# FishyUSBHub.net
KiCad netlist of a schematic drawn in EasyEDA Pro
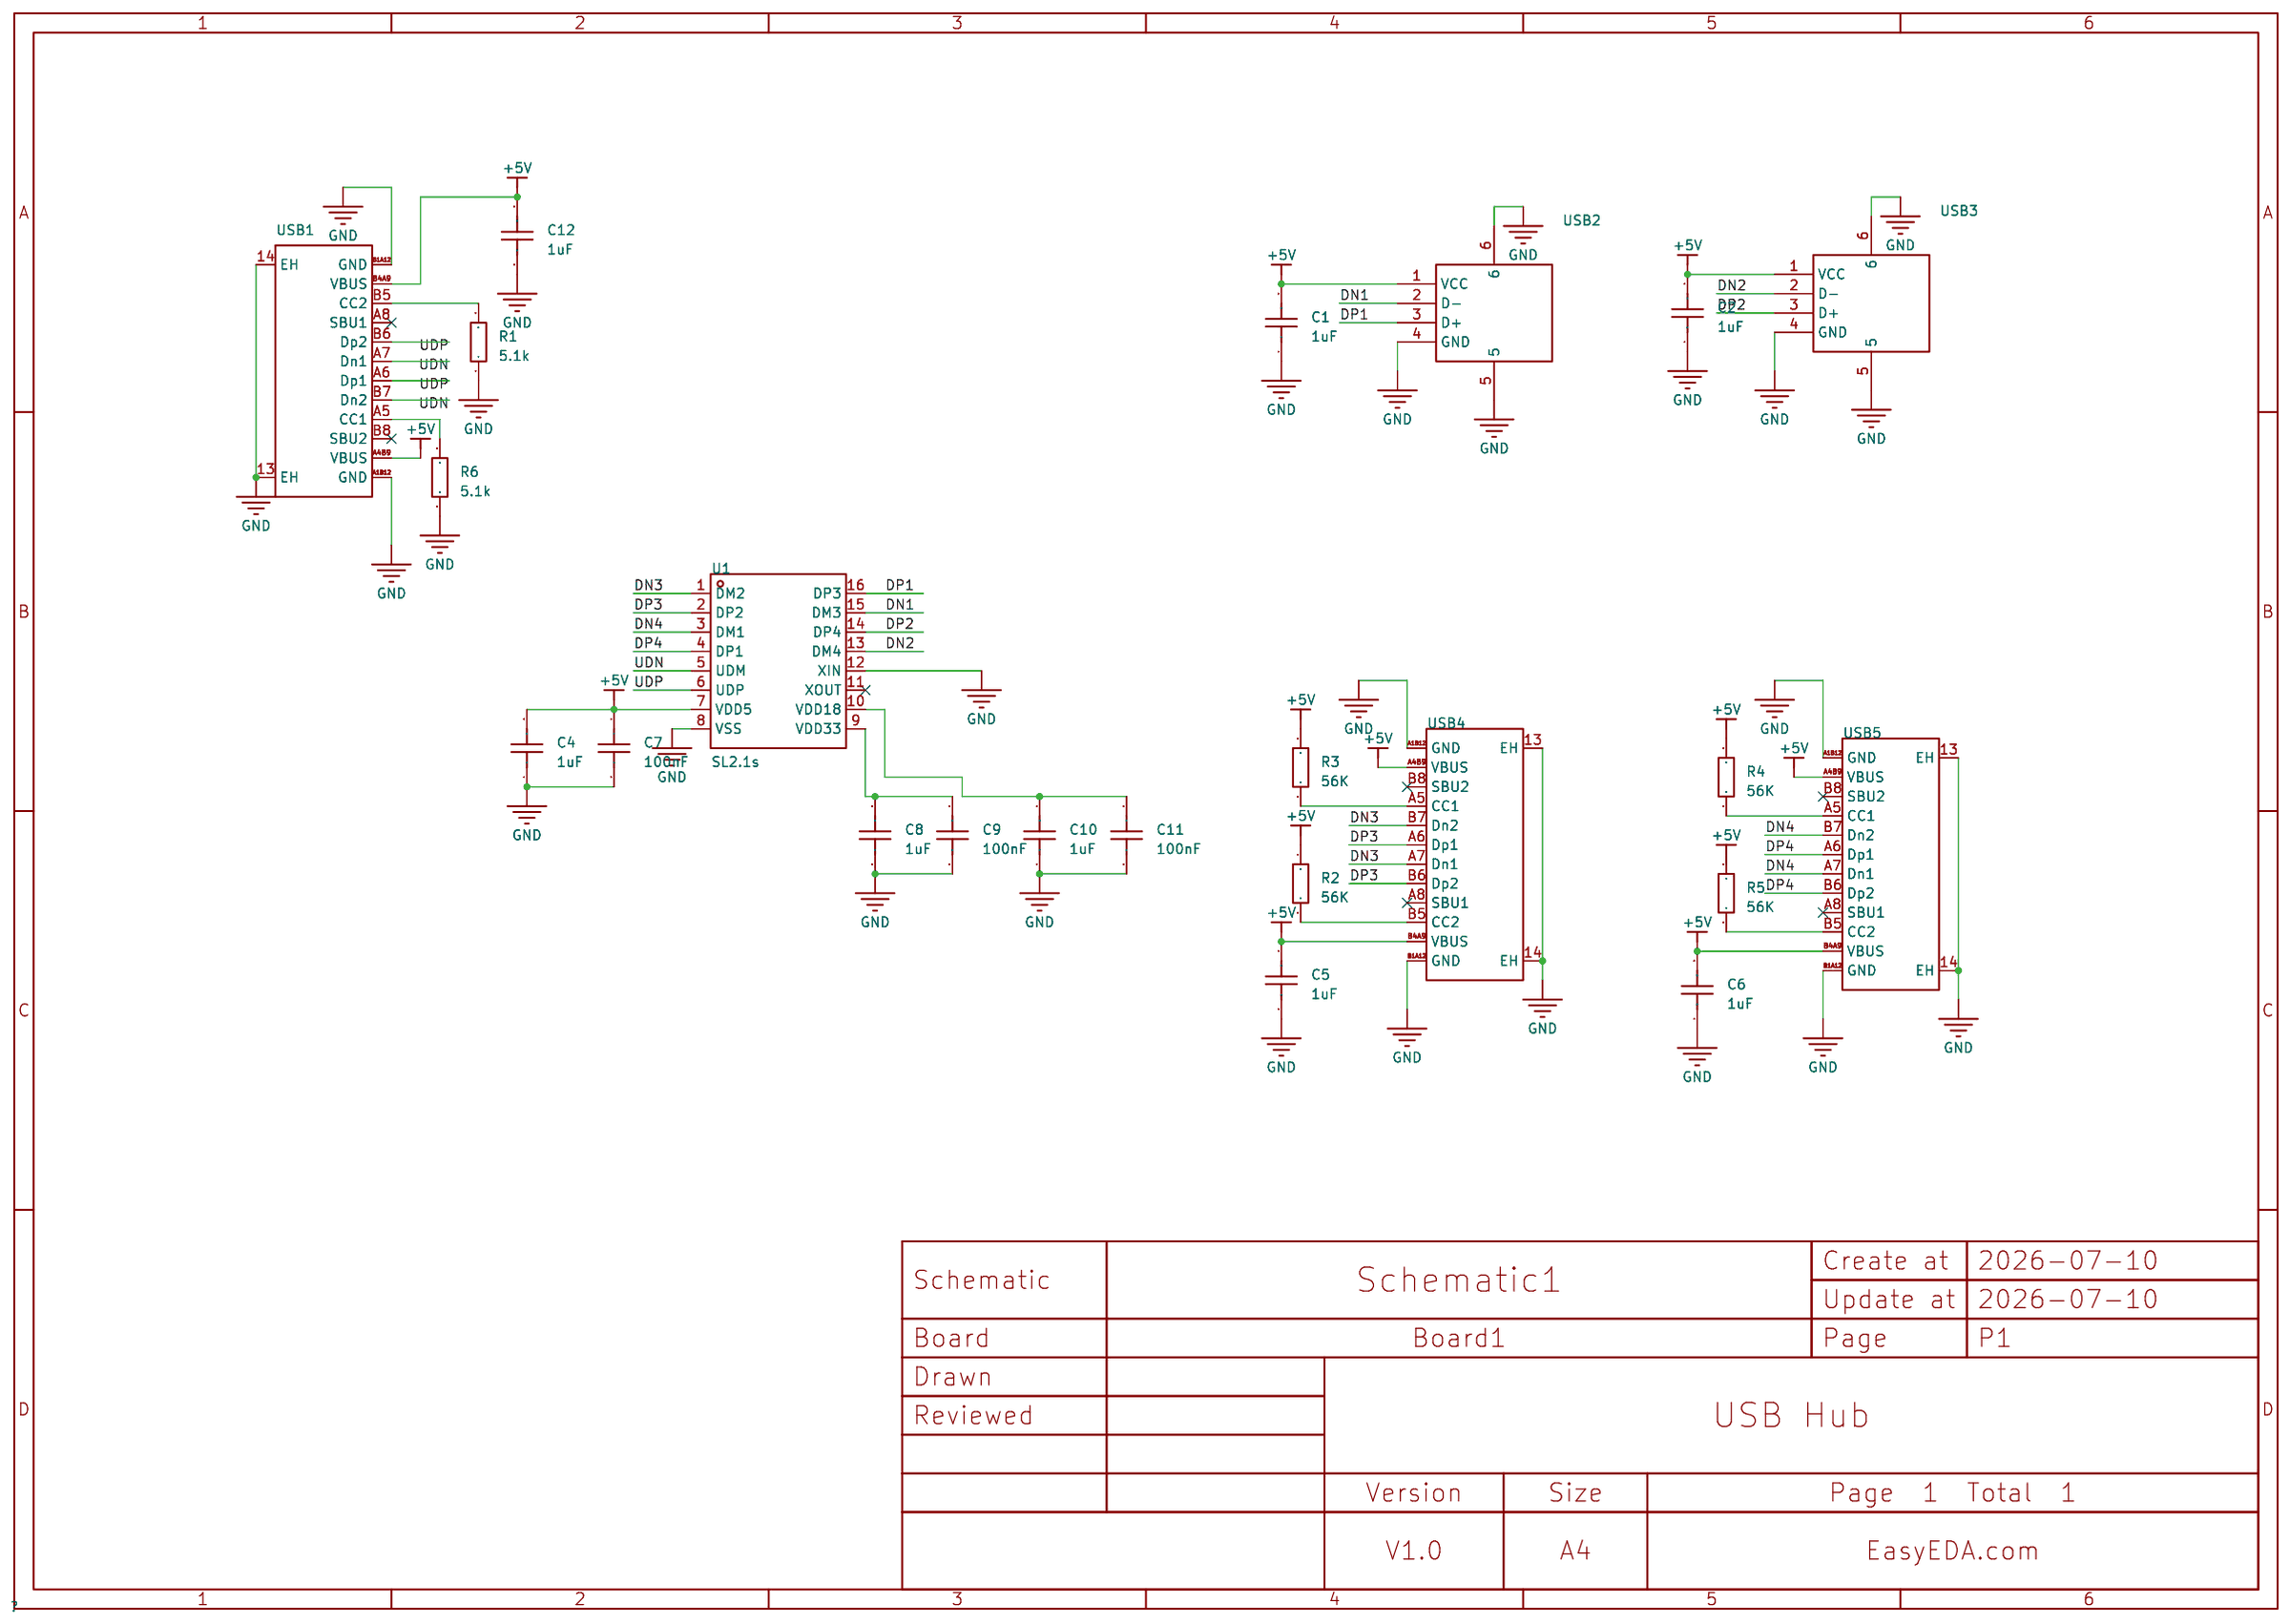
[diagram p0: schematic sheet]

(export (version "E")
  (design (tool "Eeschema 10.0.6"))
  (components
    (comp (ref "C1") (value "1uF") (footprint "easyedapro:C0603") (libsource (lib "easyedapro") (part "CAP")))
    (comp (ref "C2") (value "1uF") (footprint "easyedapro:C0603") (libsource (lib "easyedapro") (part "CAP")))
    (comp (ref "C4") (value "1uF") (footprint "easyedapro:C0603") (libsource (lib "easyedapro") (part "CAP")))
    (comp (ref "C5") (value "1uF") (footprint "easyedapro:C0603") (libsource (lib "easyedapro") (part "CAP")))
    (comp (ref "C6") (value "1uF") (footprint "easyedapro:C0603") (libsource (lib "easyedapro") (part "CAP")))
    (comp (ref "C7")
      (value "100nF")
      (footprint "easyedapro:C0603")
      (libsource (lib "easyedapro") (part "CAP"))
    )
    (comp (ref "C8") (value "1uF") (footprint "easyedapro:C0603") (libsource (lib "easyedapro") (part "CAP")))
    (comp (ref "C9")
      (value "100nF")
      (footprint "easyedapro:C0603")
      (libsource (lib "easyedapro") (part "CAP"))
    )
    (comp (ref "C10")
      (value "1uF")
      (footprint "easyedapro:C0603")
      (libsource (lib "easyedapro") (part "CAP"))
    )
    (comp (ref "C11")
      (value "100nF")
      (footprint "easyedapro:C0603")
      (libsource (lib "easyedapro") (part "CAP"))
    )
    (comp (ref "C12")
      (value "1uF")
      (footprint "easyedapro:C0603")
      (libsource (lib "easyedapro") (part "CAP"))
    )
    (comp (ref "R1")
      (value "5.1k")
      (footprint "easyedapro:R0603")
      (libsource (lib "easyedapro") (part "Res"))
    )
    (comp (ref "R2") (value "56K") (footprint "easyedapro:R0603") (libsource (lib "easyedapro") (part "Res")))
    (comp (ref "R3") (value "56K") (footprint "easyedapro:R0603") (libsource (lib "easyedapro") (part "Res")))
    (comp (ref "R4") (value "56K") (footprint "easyedapro:R0603") (libsource (lib "easyedapro") (part "Res")))
    (comp (ref "R5") (value "56K") (footprint "easyedapro:R0603") (libsource (lib "easyedapro") (part "Res")))
    (comp (ref "R6")
      (value "5.1k")
      (footprint "easyedapro:R0603")
      (libsource (lib "easyedapro") (part "Res"))
    )
    (comp (ref "U1")
      (value "SL2.1s")
      (footprint "easyedapro:SSOP-16_L4.6-W2.6-P0.53-LS4.0-BL")
      (fields (field (name "Manufacturer") "CoreChips(和芯润德)"))
      (libsource (lib "easyedapro") (part "SL2.1S"))
    )
    (comp (ref "USB1")
      (value "TYPE-C 16PIN 2MD(073)")
      (footprint "easyedapro:USB-C-SMD_TYPE-C-16PIN-2MD-073")
      (fields (field (name "Manufacturer") "SHOU HAN(首韩)"))
      (libsource (lib "easyedapro") (part "TYPE-C 16PIN 2MD(073)"))
    )
    (comp (ref "USB2")
      (value "10.0 QHHTZB6.3")
      (footprint "easyedapro:USB-A-TH_10.0QHHTZB6.3")
      (fields (field (name "Manufacturer") "SHOU HAN(首韩)"))
      (libsource (lib "easyedapro") (part "10.0 QHHTZB6.3"))
    )
    (comp (ref "USB3")
      (value "10.0 QHHTZB6.3")
      (footprint "easyedapro:USB-A-TH_10.0QHHTZB6.3")
      (fields (field (name "Manufacturer") "SHOU HAN(首韩)"))
      (libsource (lib "easyedapro") (part "10.0 QHHTZB6.3"))
    )
    (comp (ref "USB4")
      (value "TYPE-C 16PIN 2MD(073)")
      (footprint "easyedapro:USB-C-SMD_TYPE-C-16PIN-2MD-073")
      (fields (field (name "Manufacturer") "SHOU HAN(首韩)"))
      (libsource (lib "easyedapro") (part "TYPE-C 16PIN 2MD(073)"))
    )
    (comp (ref "USB5")
      (value "TYPE-C 16PIN 2MD(073)")
      (footprint "easyedapro:USB-C-SMD_TYPE-C-16PIN-2MD-073")
      (fields (field (name "Manufacturer") "SHOU HAN(首韩)"))
      (libsource (lib "easyedapro") (part "TYPE-C 16PIN 2MD(073)"))
    )
  )
  (nets
    (net (code "1") (name "+5V") (class "Default")
      (node (ref "C1") (pin "2") (pinfunction "2_2") (pintype "input"))
      (node (ref "C12") (pin "2") (pinfunction "2_2") (pintype "input"))
      (node (ref "C2") (pin "2") (pinfunction "2_2") (pintype "input"))
      (node (ref "C4") (pin "2") (pinfunction "2_2") (pintype "input"))
      (node (ref "C5") (pin "2") (pinfunction "2_2") (pintype "input"))
      (node (ref "C6") (pin "2") (pinfunction "2_2") (pintype "input"))
      (node (ref "C7") (pin "1") (pinfunction "1_1") (pintype "input"))
      (node (ref "R2") (pin "1") (pinfunction "1_1") (pintype "input"))
      (node (ref "R3") (pin "1") (pinfunction "1_1") (pintype "input"))
      (node (ref "R4") (pin "1") (pinfunction "1_1") (pintype "input"))
      (node (ref "R5") (pin "1") (pinfunction "1_1") (pintype "input"))
      (node (ref "U1") (pin "7") (pinfunction "VDD5_7") (pintype "unspecified"))
      (node (ref "USB1") (pin "A4B9") (pinfunction "VBUS_A4B9") (pintype "unspecified"))
      (node (ref "USB1") (pin "B4A9") (pinfunction "VBUS_B4A9") (pintype "unspecified"))
      (node (ref "USB2") (pin "1") (pinfunction "VCC_1") (pintype "unspecified"))
      (node (ref "USB3") (pin "1") (pinfunction "VCC_1") (pintype "unspecified"))
      (node (ref "USB4") (pin "A4B9") (pinfunction "VBUS_A4B9") (pintype "unspecified"))
      (node (ref "USB4") (pin "B4A9") (pinfunction "VBUS_B4A9") (pintype "unspecified"))
      (node (ref "USB5") (pin "A4B9") (pinfunction "VBUS_A4B9") (pintype "unspecified"))
      (node (ref "USB5") (pin "B4A9") (pinfunction "VBUS_B4A9") (pintype "unspecified"))
    )
    (net (code "2") (name "/DN1") (class "Default")
      (node (ref "U1") (pin "15") (pinfunction "DM3_15") (pintype "unspecified"))
      (node (ref "USB2") (pin "2") (pinfunction "D-_2") (pintype "unspecified"))
    )
    (net (code "3") (name "/DN2") (class "Default")
      (node (ref "U1") (pin "13") (pinfunction "DM4_13") (pintype "unspecified"))
      (node (ref "USB3") (pin "2") (pinfunction "D-_2") (pintype "unspecified"))
    )
    (net (code "4") (name "/DN3") (class "Default")
      (node (ref "U1") (pin "1") (pinfunction "DM2_1") (pintype "unspecified"))
      (node (ref "USB4") (pin "A7") (pinfunction "Dn1_A7") (pintype "unspecified"))
      (node (ref "USB4") (pin "B7") (pinfunction "Dn2_B7") (pintype "unspecified"))
    )
    (net (code "5") (name "/DN4") (class "Default")
      (node (ref "U1") (pin "3") (pinfunction "DM1_3") (pintype "unspecified"))
      (node (ref "USB5") (pin "A7") (pinfunction "Dn1_A7") (pintype "unspecified"))
      (node (ref "USB5") (pin "B7") (pinfunction "Dn2_B7") (pintype "unspecified"))
    )
    (net (code "6") (name "/DP1") (class "Default")
      (node (ref "U1") (pin "16") (pinfunction "DP3_16") (pintype "unspecified"))
      (node (ref "USB2") (pin "3") (pinfunction "D+_3") (pintype "unspecified"))
    )
    (net (code "7") (name "/DP2") (class "Default")
      (node (ref "U1") (pin "14") (pinfunction "DP4_14") (pintype "unspecified"))
      (node (ref "USB3") (pin "3") (pinfunction "D+_3") (pintype "unspecified"))
    )
    (net (code "8") (name "/DP3") (class "Default")
      (node (ref "U1") (pin "2") (pinfunction "DP2_2") (pintype "unspecified"))
      (node (ref "USB4") (pin "A6") (pinfunction "Dp1_A6") (pintype "unspecified"))
      (node (ref "USB4") (pin "B6") (pinfunction "Dp2_B6") (pintype "unspecified"))
    )
    (net (code "9") (name "/DP4") (class "Default")
      (node (ref "U1") (pin "4") (pinfunction "DP1_4") (pintype "unspecified"))
      (node (ref "USB5") (pin "A6") (pinfunction "Dp1_A6") (pintype "unspecified"))
      (node (ref "USB5") (pin "B6") (pinfunction "Dp2_B6") (pintype "unspecified"))
    )
    (net (code "10") (name "/UDN") (class "Default")
      (node (ref "U1") (pin "5") (pinfunction "UDM_5") (pintype "unspecified"))
      (node (ref "USB1") (pin "A7") (pinfunction "Dn1_A7") (pintype "unspecified"))
      (node (ref "USB1") (pin "B7") (pinfunction "Dn2_B7") (pintype "unspecified"))
    )
    (net (code "11") (name "/UDP") (class "Default")
      (node (ref "U1") (pin "6") (pinfunction "UDP_6") (pintype "unspecified"))
      (node (ref "USB1") (pin "A6") (pinfunction "Dp1_A6") (pintype "unspecified"))
      (node (ref "USB1") (pin "B6") (pinfunction "Dp2_B6") (pintype "unspecified"))
    )
    (net (code "12") (name "GND") (class "Default")
      (node (ref "C1") (pin "1") (pinfunction "1_1") (pintype "input"))
      (node (ref "C10") (pin "1") (pinfunction "1_1") (pintype "input"))
      (node (ref "C11") (pin "2") (pinfunction "2_2") (pintype "input"))
      (node (ref "C12") (pin "1") (pinfunction "1_1") (pintype "input"))
      (node (ref "C2") (pin "1") (pinfunction "1_1") (pintype "input"))
      (node (ref "C4") (pin "1") (pinfunction "1_1") (pintype "input"))
      (node (ref "C5") (pin "1") (pinfunction "1_1") (pintype "input"))
      (node (ref "C6") (pin "1") (pinfunction "1_1") (pintype "input"))
      (node (ref "C7") (pin "2") (pinfunction "2_2") (pintype "input"))
      (node (ref "C8") (pin "1") (pinfunction "1_1") (pintype "input"))
      (node (ref "C9") (pin "2") (pinfunction "2_2") (pintype "input"))
      (node (ref "R1") (pin "1") (pinfunction "1_1") (pintype "input"))
      (node (ref "R6") (pin "2") (pinfunction "2_2") (pintype "input"))
      (node (ref "U1") (pin "12") (pinfunction "XIN_12") (pintype "unspecified"))
      (node (ref "U1") (pin "8") (pinfunction "VSS_8") (pintype "unspecified"))
      (node (ref "USB1") (pin "13") (pinfunction "EH_13") (pintype "unspecified"))
      (node (ref "USB1") (pin "14") (pinfunction "EH_14") (pintype "unspecified"))
      (node (ref "USB1") (pin "A1B12") (pinfunction "GND_A1B12") (pintype "unspecified"))
      (node (ref "USB1") (pin "B1A12") (pinfunction "GND_B1A12") (pintype "unspecified"))
      (node (ref "USB2") (pin "4") (pinfunction "GND_4") (pintype "unspecified"))
      (node (ref "USB2") (pin "5") (pinfunction "5_5") (pintype "unspecified"))
      (node (ref "USB2") (pin "6") (pinfunction "6_6") (pintype "unspecified"))
      (node (ref "USB3") (pin "4") (pinfunction "GND_4") (pintype "unspecified"))
      (node (ref "USB3") (pin "5") (pinfunction "5_5") (pintype "unspecified"))
      (node (ref "USB3") (pin "6") (pinfunction "6_6") (pintype "unspecified"))
      (node (ref "USB4") (pin "13") (pinfunction "EH_13") (pintype "unspecified"))
      (node (ref "USB4") (pin "14") (pinfunction "EH_14") (pintype "unspecified"))
      (node (ref "USB4") (pin "A1B12") (pinfunction "GND_A1B12") (pintype "unspecified"))
      (node (ref "USB4") (pin "B1A12") (pinfunction "GND_B1A12") (pintype "unspecified"))
      (node (ref "USB5") (pin "13") (pinfunction "EH_13") (pintype "unspecified"))
      (node (ref "USB5") (pin "14") (pinfunction "EH_14") (pintype "unspecified"))
      (node (ref "USB5") (pin "A1B12") (pinfunction "GND_A1B12") (pintype "unspecified"))
      (node (ref "USB5") (pin "B1A12") (pinfunction "GND_B1A12") (pintype "unspecified"))
    )
    (net (code "13") (name "Net-(U1-VDD18)") (class "Default")
      (node (ref "C10") (pin "2") (pinfunction "2_2") (pintype "input"))
      (node (ref "C11") (pin "1") (pinfunction "1_1") (pintype "input"))
      (node (ref "U1") (pin "10") (pinfunction "VDD18_10") (pintype "unspecified"))
    )
    (net (code "14") (name "Net-(U1-VDD33)") (class "Default")
      (node (ref "C8") (pin "2") (pinfunction "2_2") (pintype "input"))
      (node (ref "C9") (pin "1") (pinfunction "1_1") (pintype "input"))
      (node (ref "U1") (pin "9") (pinfunction "VDD33_9") (pintype "unspecified"))
    )
    (net (code "15") (name "Net-(USB1-CC1)") (class "Default")
      (node (ref "R6") (pin "1") (pinfunction "1_1") (pintype "input"))
      (node (ref "USB1") (pin "A5") (pinfunction "CC1_A5") (pintype "unspecified"))
    )
    (net (code "16") (name "Net-(USB1-CC2)") (class "Default")
      (node (ref "R1") (pin "2") (pinfunction "2_2") (pintype "input"))
      (node (ref "USB1") (pin "B5") (pinfunction "CC2_B5") (pintype "unspecified"))
    )
    (net (code "17") (name "Net-(USB4-CC1)") (class "Default")
      (node (ref "R3") (pin "2") (pinfunction "2_2") (pintype "input"))
      (node (ref "USB4") (pin "A5") (pinfunction "CC1_A5") (pintype "unspecified"))
    )
    (net (code "18") (name "Net-(USB4-CC2)") (class "Default")
      (node (ref "R2") (pin "2") (pinfunction "2_2") (pintype "input"))
      (node (ref "USB4") (pin "B5") (pinfunction "CC2_B5") (pintype "unspecified"))
    )
    (net (code "19") (name "Net-(USB5-CC1)") (class "Default")
      (node (ref "R4") (pin "2") (pinfunction "2_2") (pintype "input"))
      (node (ref "USB5") (pin "A5") (pinfunction "CC1_A5") (pintype "unspecified"))
    )
    (net (code "20") (name "Net-(USB5-CC2)") (class "Default")
      (node (ref "R5") (pin "2") (pinfunction "2_2") (pintype "input"))
      (node (ref "USB5") (pin "B5") (pinfunction "CC2_B5") (pintype "unspecified"))
    )
    (net (code "21") (name "unconnected-(U1-XOUT-Pad11)") (class "Default")
      (node (ref "U1") (pin "11") (pinfunction "XOUT_11") (pintype "unspecified+no_connect"))
    )
    (net (code "22") (name "unconnected-(USB1-SBU1-PadA8)") (class "Default")
      (node (ref "USB1") (pin "A8") (pinfunction "SBU1_A8") (pintype "unspecified+no_connect"))
    )
    (net (code "23") (name "unconnected-(USB1-SBU2-PadB8)") (class "Default")
      (node (ref "USB1") (pin "B8") (pinfunction "SBU2_B8") (pintype "unspecified+no_connect"))
    )
    (net (code "24") (name "unconnected-(USB4-SBU1-PadA8)") (class "Default")
      (node (ref "USB4") (pin "A8") (pinfunction "SBU1_A8") (pintype "unspecified+no_connect"))
    )
    (net (code "25") (name "unconnected-(USB4-SBU2-PadB8)") (class "Default")
      (node (ref "USB4") (pin "B8") (pinfunction "SBU2_B8") (pintype "unspecified+no_connect"))
    )
    (net (code "26") (name "unconnected-(USB5-SBU1-PadA8)") (class "Default")
      (node (ref "USB5") (pin "A8") (pinfunction "SBU1_A8") (pintype "unspecified+no_connect"))
    )
    (net (code "27") (name "unconnected-(USB5-SBU2-PadB8)") (class "Default")
      (node (ref "USB5") (pin "B8") (pinfunction "SBU2_B8") (pintype "unspecified+no_connect"))
    )
  )
)
